# QSTL_M12C_BNC_v2.net
KiCad netlist of a schematic drawn in Altium Designer
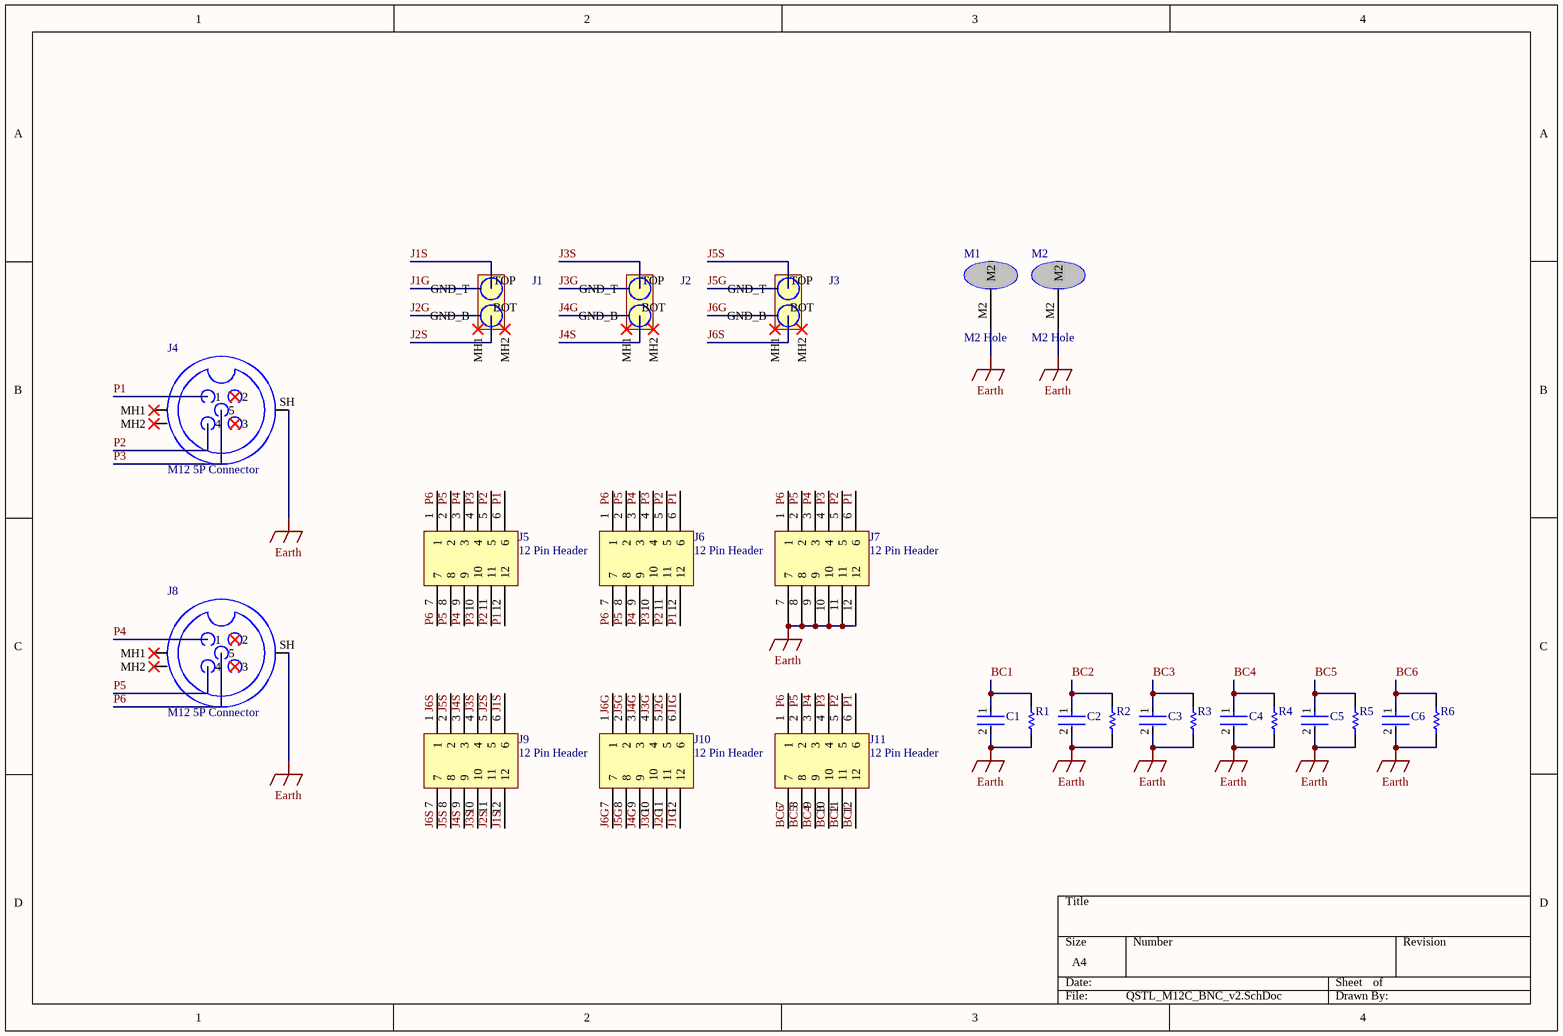
[diagram p0: QSTL_M12C_BNC_v2.SchDoc]

(export (version "E")
  (design (tool "Eeschema 10.0.6"))
  (components
    (comp (ref "C1")
      (value "Murata 0805")
      (footprint "FP-GRM21B-0_15-MFG")
      (description "Chip Multilayer Ceramic Capacitors for General Purpose, 0805, 10uF, X7R, 15%, 10%, 10V")
      (fields (field (name "TOLERANCE") "10%"))
      (libsource (lib "Altium Content Vault") (part "b4654b650e69147ec39a6b967a45e02"))
    )
    (comp (ref "C2")
      (value "Murata 0805")
      (footprint "FP-GRM21B-0_15-MFG")
      (description "Chip Multilayer Ceramic Capacitors for General Purpose, 0805, 10uF, X7R, 15%, 10%, 10V")
      (fields (field (name "TOLERANCE") "10%"))
      (libsource (lib "Altium Content Vault") (part "b4654b650e69147ec39a6b967a45e02"))
    )
    (comp (ref "C3")
      (value "Murata 0805")
      (footprint "FP-GRM21B-0_15-MFG")
      (description "Chip Multilayer Ceramic Capacitors for General Purpose, 0805, 10uF, X7R, 15%, 10%, 10V")
      (fields (field (name "TOLERANCE") "10%"))
      (libsource (lib "Altium Content Vault") (part "b4654b650e69147ec39a6b967a45e02"))
    )
    (comp (ref "C4")
      (value "Murata 0805")
      (footprint "FP-GRM21B-0_15-MFG")
      (description "Chip Multilayer Ceramic Capacitors for General Purpose, 0805, 10uF, X7R, 15%, 10%, 10V")
      (fields (field (name "TOLERANCE") "10%"))
      (libsource (lib "Altium Content Vault") (part "b4654b650e69147ec39a6b967a45e02"))
    )
    (comp (ref "C5")
      (value "Murata 0805")
      (footprint "FP-GRM21B-0_15-MFG")
      (description "Chip Multilayer Ceramic Capacitors for General Purpose, 0805, 10uF, X7R, 15%, 10%, 10V")
      (fields (field (name "TOLERANCE") "10%"))
      (libsource (lib "Altium Content Vault") (part "b4654b650e69147ec39a6b967a45e02"))
    )
    (comp (ref "C6")
      (value "Murata 0805")
      (footprint "FP-GRM21B-0_15-MFG")
      (description "Chip Multilayer Ceramic Capacitors for General Purpose, 0805, 10uF, X7R, 15%, 10%, 10V")
      (fields (field (name "TOLERANCE") "10%"))
      (libsource (lib "Altium Content Vault") (part "b4654b650e69147ec39a6b967a45e02"))
    )
    (comp (ref "J1")
      (value "Isolated Stacked BNC")
      (footprint "031-6575")
      (description "https://www.digikey.ca/en/products/detail/amphenol-rf/031-6575/4037241")
      (libsource (lib "QSTL_M12C_BNC") (part "031-6575"))
    )
    (comp (ref "J2")
      (value "Isolated Stacked BNC")
      (footprint "031-6575")
      (description "https://www.digikey.ca/en/products/detail/amphenol-rf/031-6575/4037241")
      (libsource (lib "QSTL_M12C_BNC") (part "031-6575"))
    )
    (comp (ref "J3")
      (value "Isolated Stacked BNC")
      (footprint "031-6575")
      (description "https://www.digikey.ca/en/products/detail/amphenol-rf/031-6575/4037241")
      (libsource (lib "QSTL_M12C_BNC") (part "031-6575"))
    )
    (comp (ref "J4")
      (value "M12 5P Connector")
      (footprint "861-B05-213R004")
      (libsource (lib "QSTL_M12C_BNC") (part "861-B05-213R004"))
    )
    (comp (ref "J5")
      (value "12 Pin Header")
      (footprint "PZ254-2-06-S")
      (description "https://jlcpcb.com/partdetail/HCTL-PZ254_2_06S/C3294464")
      (libsource (lib "QSTL_M12C_BNC") (part "PZ254-2-06-S"))
    )
    (comp (ref "J6")
      (value "12 Pin Header")
      (footprint "PZ254-2-06-S")
      (description "https://jlcpcb.com/partdetail/HCTL-PZ254_2_06S/C3294464")
      (libsource (lib "QSTL_M12C_BNC") (part "PZ254-2-06-S"))
    )
    (comp (ref "J7")
      (value "12 Pin Header")
      (footprint "PZ254-2-06-S")
      (description "https://jlcpcb.com/partdetail/HCTL-PZ254_2_06S/C3294464")
      (libsource (lib "QSTL_M12C_BNC") (part "PZ254-2-06-S"))
    )
    (comp (ref "J8")
      (value "M12 5P Connector")
      (footprint "861-B05-213R004")
      (libsource (lib "QSTL_M12C_BNC") (part "861-B05-213R004"))
    )
    (comp (ref "J9")
      (value "12 Pin Header")
      (footprint "PZ254-2-06-S")
      (description "https://jlcpcb.com/partdetail/HCTL-PZ254_2_06S/C3294464")
      (libsource (lib "QSTL_M12C_BNC") (part "PZ254-2-06-S"))
    )
    (comp (ref "J10")
      (value "12 Pin Header")
      (footprint "PZ254-2-06-S")
      (description "https://jlcpcb.com/partdetail/HCTL-PZ254_2_06S/C3294464")
      (libsource (lib "QSTL_M12C_BNC") (part "PZ254-2-06-S"))
    )
    (comp (ref "J11")
      (value "12 Pin Header")
      (footprint "PZ254-2-06-S")
      (description "https://jlcpcb.com/partdetail/HCTL-PZ254_2_06S/C3294464")
      (libsource (lib "QSTL_M12C_BNC") (part "PZ254-2-06-S"))
    )
    (comp (ref "M1")
      (value "M2 Hole")
      (footprint "M2_Hole")
      (libsource (lib "QSTL_M12C_BNC") (part "M2_Hole"))
    )
    (comp (ref "M2")
      (value "M2 Hole")
      (footprint "M2_Hole")
      (libsource (lib "QSTL_M12C_BNC") (part "M2_Hole"))
    )
    (comp (ref "R1")
      (value "Panasonic 0805")
      (footprint "RESC2013X60X40LL20T25")
      (fields (field (name "MANUFACTURER") "Panasonic") (field (name "PART NUMBER") "ERA6AEB222V"))
      (libsource (lib "Altium Content Vault") (part "RES"))
    )
    (comp (ref "R2")
      (value "Panasonic 0805")
      (footprint "RESC2013X60X40LL20T25")
      (fields (field (name "MANUFACTURER") "Panasonic") (field (name "PART NUMBER") "ERA6AEB222V"))
      (libsource (lib "Altium Content Vault") (part "RES"))
    )
    (comp (ref "R3")
      (value "Panasonic 0805")
      (footprint "RESC2013X60X40LL20T25")
      (fields (field (name "MANUFACTURER") "Panasonic") (field (name "PART NUMBER") "ERA6AEB222V"))
      (libsource (lib "Altium Content Vault") (part "RES"))
    )
    (comp (ref "R4")
      (value "Panasonic 0805")
      (footprint "RESC2013X60X40LL20T25")
      (fields (field (name "MANUFACTURER") "Panasonic") (field (name "PART NUMBER") "ERA6AEB222V"))
      (libsource (lib "Altium Content Vault") (part "RES"))
    )
    (comp (ref "R5")
      (value "Panasonic 0805")
      (footprint "RESC2013X60X40LL20T25")
      (fields (field (name "MANUFACTURER") "Panasonic") (field (name "PART NUMBER") "ERA6AEB222V"))
      (libsource (lib "Altium Content Vault") (part "RES"))
    )
    (comp (ref "R6")
      (value "Panasonic 0805")
      (footprint "RESC2013X60X40LL20T25")
      (fields (field (name "MANUFACTURER") "Panasonic") (field (name "PART NUMBER") "ERA6AEB222V"))
      (libsource (lib "Altium Content Vault") (part "RES"))
    )
  )
  (nets
    (net (code "1") (name "/BC1") (class "Default")
      (node (ref "C1") (pin "1") (pinfunction "1_1") (pintype "passive"))
      (node (ref "J11") (pin "12") (pinfunction "12_12") (pintype "passive"))
      (node (ref "R1") (pin "1") (pinfunction "1_1") (pintype "passive"))
    )
    (net (code "2") (name "/BC2") (class "Default")
      (node (ref "C2") (pin "1") (pinfunction "1_1") (pintype "passive"))
      (node (ref "J11") (pin "11") (pinfunction "11_11") (pintype "passive"))
      (node (ref "R2") (pin "1") (pinfunction "1_1") (pintype "passive"))
    )
    (net (code "3") (name "/BC3") (class "Default")
      (node (ref "C3") (pin "1") (pinfunction "1_1") (pintype "passive"))
      (node (ref "J11") (pin "10") (pinfunction "10_10") (pintype "passive"))
      (node (ref "R3") (pin "1") (pinfunction "1_1") (pintype "passive"))
    )
    (net (code "4") (name "/BC4") (class "Default")
      (node (ref "C4") (pin "1") (pinfunction "1_1") (pintype "passive"))
      (node (ref "J11") (pin "9") (pinfunction "9_9") (pintype "passive"))
      (node (ref "R4") (pin "1") (pinfunction "1_1") (pintype "passive"))
    )
    (net (code "5") (name "/BC5") (class "Default")
      (node (ref "C5") (pin "1") (pinfunction "1_1") (pintype "passive"))
      (node (ref "J11") (pin "8") (pinfunction "8_8") (pintype "passive"))
      (node (ref "R5") (pin "1") (pinfunction "1_1") (pintype "passive"))
    )
    (net (code "6") (name "/BC6") (class "Default")
      (node (ref "C6") (pin "1") (pinfunction "1_1") (pintype "passive"))
      (node (ref "J11") (pin "7") (pinfunction "7_7") (pintype "passive"))
      (node (ref "R6") (pin "1") (pinfunction "1_1") (pintype "passive"))
    )
    (net (code "7") (name "/J1G") (class "Default")
      (node (ref "J1") (pin "GND_T") (pinfunction "GND_T_GND_T") (pintype "passive"))
      (node (ref "J10") (pin "12") (pinfunction "12_12") (pintype "passive"))
      (node (ref "J10") (pin "6") (pinfunction "6_6") (pintype "passive"))
    )
    (net (code "8") (name "/J1S") (class "Default")
      (node (ref "J1") (pin "TOP") (pinfunction "TOP_TOP") (pintype "passive"))
      (node (ref "J9") (pin "12") (pinfunction "12_12") (pintype "passive"))
      (node (ref "J9") (pin "6") (pinfunction "6_6") (pintype "passive"))
    )
    (net (code "9") (name "/J2G") (class "Default")
      (node (ref "J1") (pin "GND_B") (pinfunction "GND_B_GND_B") (pintype "passive"))
      (node (ref "J10") (pin "11") (pinfunction "11_11") (pintype "passive"))
      (node (ref "J10") (pin "5") (pinfunction "5_5") (pintype "passive"))
    )
    (net (code "10") (name "/J2S") (class "Default")
      (node (ref "J1") (pin "BOT") (pinfunction "BOT_BOT") (pintype "passive"))
      (node (ref "J9") (pin "11") (pinfunction "11_11") (pintype "passive"))
      (node (ref "J9") (pin "5") (pinfunction "5_5") (pintype "passive"))
    )
    (net (code "11") (name "/J3G") (class "Default")
      (node (ref "J10") (pin "10") (pinfunction "10_10") (pintype "passive"))
      (node (ref "J10") (pin "4") (pinfunction "4_4") (pintype "passive"))
      (node (ref "J2") (pin "GND_T") (pinfunction "GND_T_GND_T") (pintype "passive"))
    )
    (net (code "12") (name "/J3S") (class "Default")
      (node (ref "J2") (pin "TOP") (pinfunction "TOP_TOP") (pintype "passive"))
      (node (ref "J9") (pin "10") (pinfunction "10_10") (pintype "passive"))
      (node (ref "J9") (pin "4") (pinfunction "4_4") (pintype "passive"))
    )
    (net (code "13") (name "/J4G") (class "Default")
      (node (ref "J10") (pin "3") (pinfunction "3_3") (pintype "passive"))
      (node (ref "J10") (pin "9") (pinfunction "9_9") (pintype "passive"))
      (node (ref "J2") (pin "GND_B") (pinfunction "GND_B_GND_B") (pintype "passive"))
    )
    (net (code "14") (name "/J4S") (class "Default")
      (node (ref "J2") (pin "BOT") (pinfunction "BOT_BOT") (pintype "passive"))
      (node (ref "J9") (pin "3") (pinfunction "3_3") (pintype "passive"))
      (node (ref "J9") (pin "9") (pinfunction "9_9") (pintype "passive"))
    )
    (net (code "15") (name "/J5G") (class "Default")
      (node (ref "J10") (pin "2") (pinfunction "2_2") (pintype "passive"))
      (node (ref "J10") (pin "8") (pinfunction "8_8") (pintype "passive"))
      (node (ref "J3") (pin "GND_T") (pinfunction "GND_T_GND_T") (pintype "passive"))
    )
    (net (code "16") (name "/J5S") (class "Default")
      (node (ref "J3") (pin "TOP") (pinfunction "TOP_TOP") (pintype "passive"))
      (node (ref "J9") (pin "2") (pinfunction "2_2") (pintype "passive"))
      (node (ref "J9") (pin "8") (pinfunction "8_8") (pintype "passive"))
    )
    (net (code "17") (name "/J6G") (class "Default")
      (node (ref "J10") (pin "1") (pinfunction "1_1") (pintype "passive"))
      (node (ref "J10") (pin "7") (pinfunction "7_7") (pintype "passive"))
      (node (ref "J3") (pin "GND_B") (pinfunction "GND_B_GND_B") (pintype "passive"))
    )
    (net (code "18") (name "/J6S") (class "Default")
      (node (ref "J3") (pin "BOT") (pinfunction "BOT_BOT") (pintype "passive"))
      (node (ref "J9") (pin "1") (pinfunction "1_1") (pintype "passive"))
      (node (ref "J9") (pin "7") (pinfunction "7_7") (pintype "passive"))
    )
    (net (code "19") (name "/P1") (class "Default")
      (node (ref "J11") (pin "6") (pinfunction "6_6") (pintype "passive"))
      (node (ref "J4") (pin "1") (pinfunction "1_1") (pintype "passive"))
      (node (ref "J5") (pin "12") (pinfunction "12_12") (pintype "passive"))
      (node (ref "J5") (pin "6") (pinfunction "6_6") (pintype "passive"))
      (node (ref "J6") (pin "12") (pinfunction "12_12") (pintype "passive"))
      (node (ref "J6") (pin "6") (pinfunction "6_6") (pintype "passive"))
      (node (ref "J7") (pin "6") (pinfunction "6_6") (pintype "passive"))
    )
    (net (code "20") (name "/P2") (class "Default")
      (node (ref "J11") (pin "5") (pinfunction "5_5") (pintype "passive"))
      (node (ref "J4") (pin "4") (pinfunction "4_4") (pintype "passive"))
      (node (ref "J5") (pin "11") (pinfunction "11_11") (pintype "passive"))
      (node (ref "J5") (pin "5") (pinfunction "5_5") (pintype "passive"))
      (node (ref "J6") (pin "11") (pinfunction "11_11") (pintype "passive"))
      (node (ref "J6") (pin "5") (pinfunction "5_5") (pintype "passive"))
      (node (ref "J7") (pin "5") (pinfunction "5_5") (pintype "passive"))
    )
    (net (code "21") (name "/P3") (class "Default")
      (node (ref "J11") (pin "4") (pinfunction "4_4") (pintype "passive"))
      (node (ref "J4") (pin "5") (pinfunction "5_5") (pintype "passive"))
      (node (ref "J5") (pin "10") (pinfunction "10_10") (pintype "passive"))
      (node (ref "J5") (pin "4") (pinfunction "4_4") (pintype "passive"))
      (node (ref "J6") (pin "10") (pinfunction "10_10") (pintype "passive"))
      (node (ref "J6") (pin "4") (pinfunction "4_4") (pintype "passive"))
      (node (ref "J7") (pin "4") (pinfunction "4_4") (pintype "passive"))
    )
    (net (code "22") (name "/P4") (class "Default")
      (node (ref "J11") (pin "3") (pinfunction "3_3") (pintype "passive"))
      (node (ref "J5") (pin "3") (pinfunction "3_3") (pintype "passive"))
      (node (ref "J5") (pin "9") (pinfunction "9_9") (pintype "passive"))
      (node (ref "J6") (pin "3") (pinfunction "3_3") (pintype "passive"))
      (node (ref "J6") (pin "9") (pinfunction "9_9") (pintype "passive"))
      (node (ref "J7") (pin "3") (pinfunction "3_3") (pintype "passive"))
      (node (ref "J8") (pin "1") (pinfunction "1_1") (pintype "passive"))
    )
    (net (code "23") (name "/P5") (class "Default")
      (node (ref "J11") (pin "2") (pinfunction "2_2") (pintype "passive"))
      (node (ref "J5") (pin "2") (pinfunction "2_2") (pintype "passive"))
      (node (ref "J5") (pin "8") (pinfunction "8_8") (pintype "passive"))
      (node (ref "J6") (pin "2") (pinfunction "2_2") (pintype "passive"))
      (node (ref "J6") (pin "8") (pinfunction "8_8") (pintype "passive"))
      (node (ref "J7") (pin "2") (pinfunction "2_2") (pintype "passive"))
      (node (ref "J8") (pin "4") (pinfunction "4_4") (pintype "passive"))
    )
    (net (code "24") (name "/P6") (class "Default")
      (node (ref "J11") (pin "1") (pinfunction "1_1") (pintype "passive"))
      (node (ref "J5") (pin "1") (pinfunction "1_1") (pintype "passive"))
      (node (ref "J5") (pin "7") (pinfunction "7_7") (pintype "passive"))
      (node (ref "J6") (pin "1") (pinfunction "1_1") (pintype "passive"))
      (node (ref "J6") (pin "7") (pinfunction "7_7") (pintype "passive"))
      (node (ref "J7") (pin "1") (pinfunction "1_1") (pintype "passive"))
      (node (ref "J8") (pin "5") (pinfunction "5_5") (pintype "passive"))
    )
    (net (code "25") (name "Earth") (class "Default")
      (node (ref "C1") (pin "2") (pinfunction "2_2") (pintype "passive"))
      (node (ref "C2") (pin "2") (pinfunction "2_2") (pintype "passive"))
      (node (ref "C3") (pin "2") (pinfunction "2_2") (pintype "passive"))
      (node (ref "C4") (pin "2") (pinfunction "2_2") (pintype "passive"))
      (node (ref "C5") (pin "2") (pinfunction "2_2") (pintype "passive"))
      (node (ref "C6") (pin "2") (pinfunction "2_2") (pintype "passive"))
      (node (ref "J4") (pin "SH") (pinfunction "SH_SH") (pintype "passive"))
      (node (ref "J7") (pin "10") (pinfunction "10_10") (pintype "passive"))
      (node (ref "J7") (pin "11") (pinfunction "11_11") (pintype "passive"))
      (node (ref "J7") (pin "12") (pinfunction "12_12") (pintype "passive"))
      (node (ref "J7") (pin "7") (pinfunction "7_7") (pintype "passive"))
      (node (ref "J7") (pin "8") (pinfunction "8_8") (pintype "passive"))
      (node (ref "J7") (pin "9") (pinfunction "9_9") (pintype "passive"))
      (node (ref "J8") (pin "SH") (pinfunction "SH_SH") (pintype "passive"))
      (node (ref "M1") (pin "M2") (pinfunction "M2_M2") (pintype "passive"))
      (node (ref "M2") (pin "M2") (pinfunction "M2_M2") (pintype "passive"))
      (node (ref "R1") (pin "2") (pinfunction "2_2") (pintype "passive"))
      (node (ref "R2") (pin "2") (pinfunction "2_2") (pintype "passive"))
      (node (ref "R3") (pin "2") (pinfunction "2_2") (pintype "passive"))
      (node (ref "R4") (pin "2") (pinfunction "2_2") (pintype "passive"))
      (node (ref "R5") (pin "2") (pinfunction "2_2") (pintype "passive"))
      (node (ref "R6") (pin "2") (pinfunction "2_2") (pintype "passive"))
    )
    (net (code "26") (name "unconnected-(J1-PadMH1)") (class "Default")
      (node (ref "J1") (pin "MH1") (pinfunction "MH1_MH1") (pintype "passive+no_connect"))
    )
    (net (code "27") (name "unconnected-(J1-PadMH2)") (class "Default")
      (node (ref "J1") (pin "MH2") (pinfunction "MH2_MH2") (pintype "passive+no_connect"))
    )
    (net (code "28") (name "unconnected-(J2-PadMH1)") (class "Default")
      (node (ref "J2") (pin "MH1") (pinfunction "MH1_MH1") (pintype "passive+no_connect"))
    )
    (net (code "29") (name "unconnected-(J2-PadMH2)") (class "Default")
      (node (ref "J2") (pin "MH2") (pinfunction "MH2_MH2") (pintype "passive+no_connect"))
    )
    (net (code "30") (name "unconnected-(J3-PadMH1)") (class "Default")
      (node (ref "J3") (pin "MH1") (pinfunction "MH1_MH1") (pintype "passive+no_connect"))
    )
    (net (code "31") (name "unconnected-(J3-PadMH2)") (class "Default")
      (node (ref "J3") (pin "MH2") (pinfunction "MH2_MH2") (pintype "passive+no_connect"))
    )
    (net (code "32") (name "unconnected-(J4-Pad2)") (class "Default")
      (node (ref "J4") (pin "2") (pinfunction "2_2") (pintype "passive+no_connect"))
    )
    (net (code "33") (name "unconnected-(J4-Pad3)") (class "Default")
      (node (ref "J4") (pin "3") (pinfunction "3_3") (pintype "passive+no_connect"))
    )
    (net (code "34") (name "unconnected-(J4-PadMH1)") (class "Default")
      (node (ref "J4") (pin "MH1") (pinfunction "MH1_MH1") (pintype "passive"))
    )
    (net (code "35") (name "unconnected-(J4-PadMH2)") (class "Default")
      (node (ref "J4") (pin "MH2") (pinfunction "MH2_MH2") (pintype "passive"))
    )
    (net (code "36") (name "unconnected-(J8-Pad2)") (class "Default")
      (node (ref "J8") (pin "2") (pinfunction "2_2") (pintype "passive+no_connect"))
    )
    (net (code "37") (name "unconnected-(J8-Pad3)") (class "Default")
      (node (ref "J8") (pin "3") (pinfunction "3_3") (pintype "passive+no_connect"))
    )
    (net (code "38") (name "unconnected-(J8-PadMH1)") (class "Default")
      (node (ref "J8") (pin "MH1") (pinfunction "MH1_MH1") (pintype "passive"))
    )
    (net (code "39") (name "unconnected-(J8-PadMH2)") (class "Default")
      (node (ref "J8") (pin "MH2") (pinfunction "MH2_MH2") (pintype "passive"))
    )
  )
)
